# Telex-I.net
KiCad netlist of a schematic drawn in EAGLE
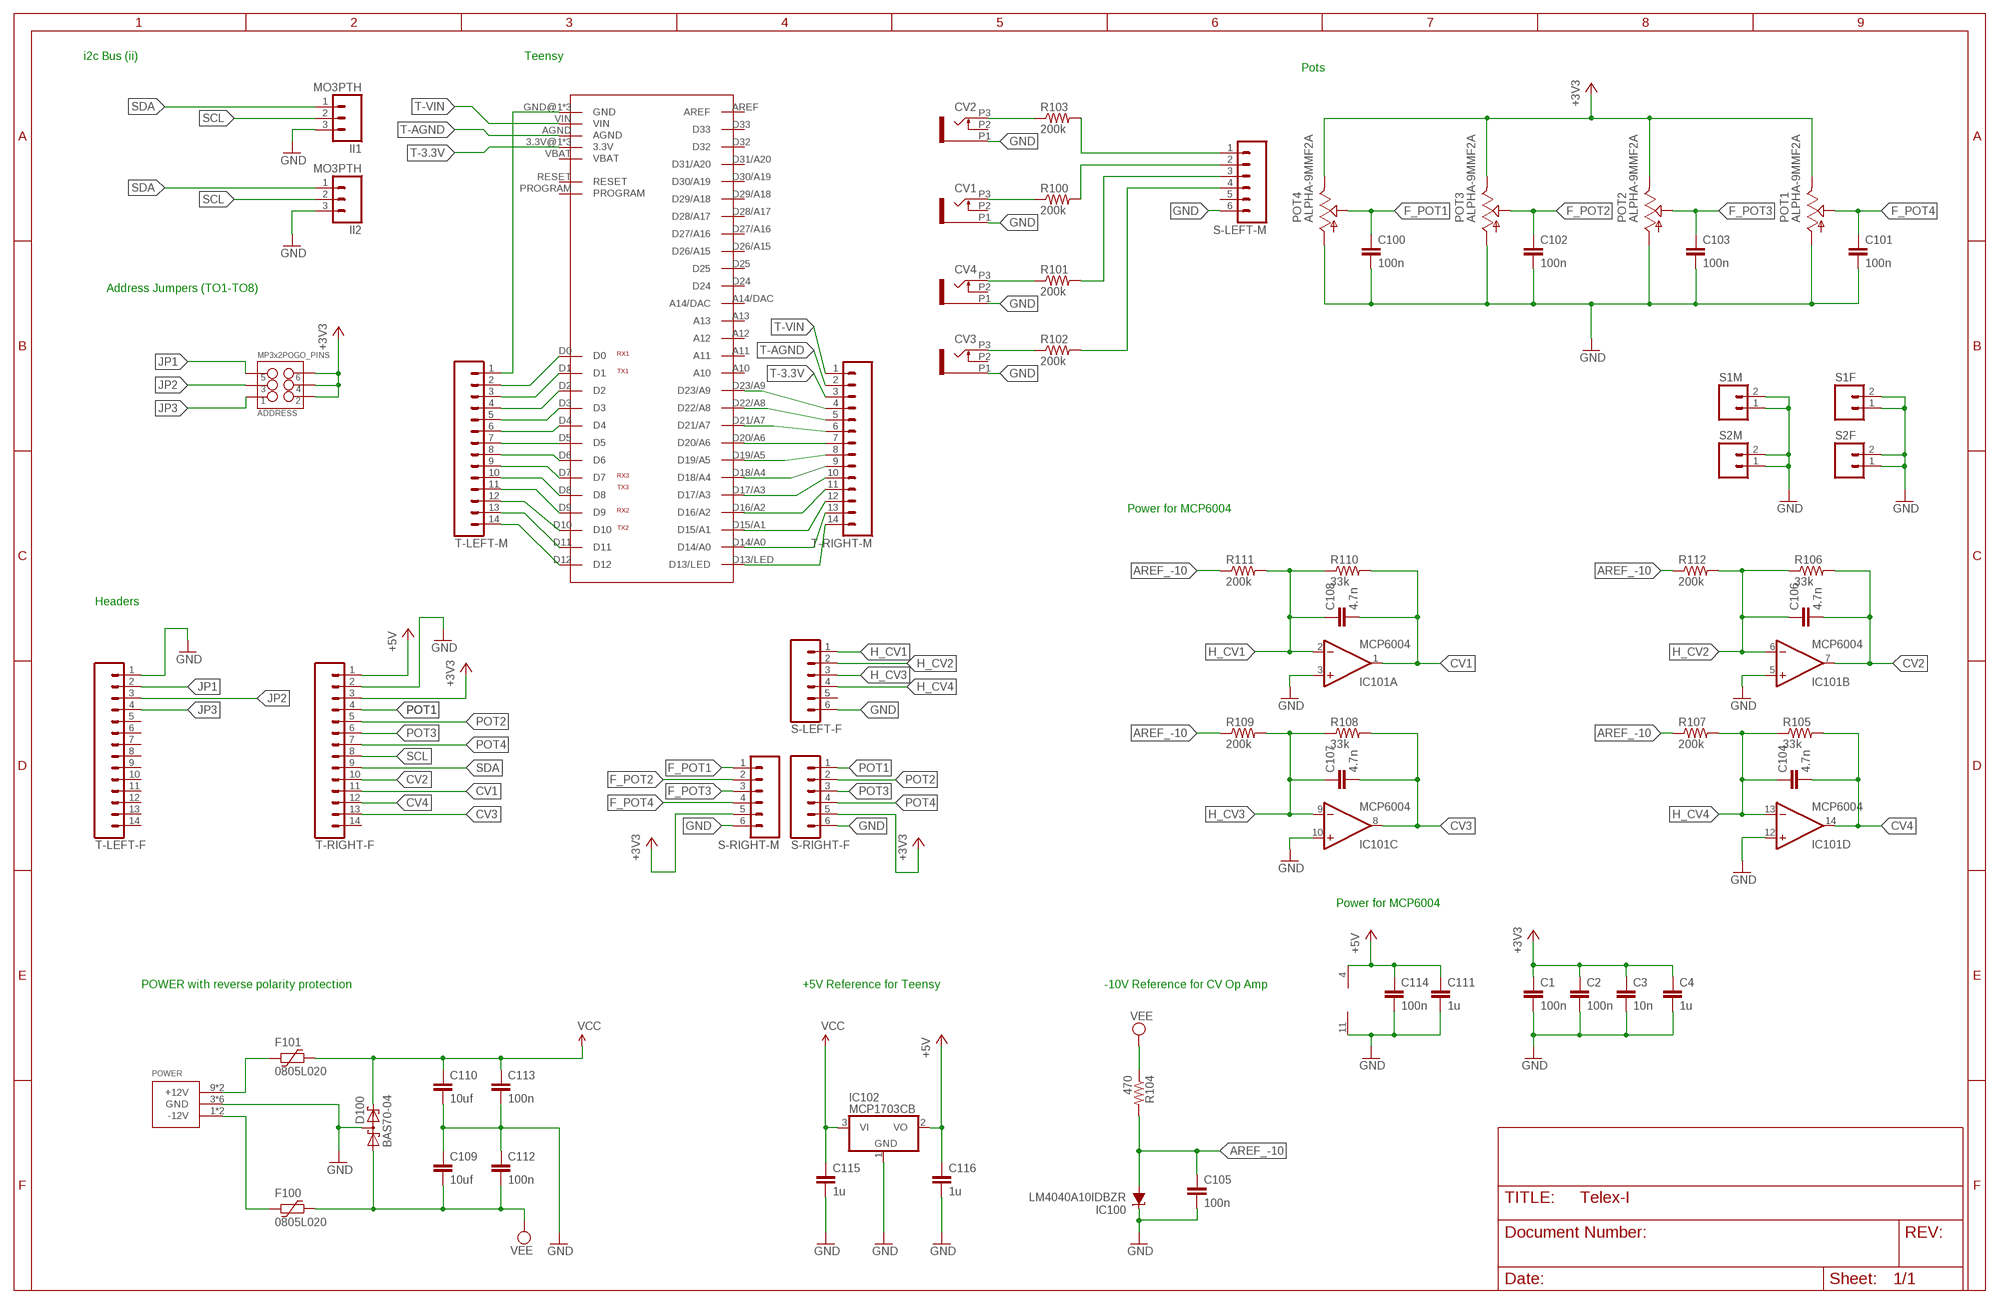
[diagram p0: schematic, sheet 1]

(export (version "E")
  (design (tool "Eeschema 10.0.6"))
  (components
    (comp (ref "ADDRESS")
      (value "MP3x2POGO_PINS")
      (footprint "eagle-import:2X3_POGO")
      (libsource (lib "eagle-import") (part "M03X2POGO_PINS"))
    )
    (comp (ref "C1")
      (value "100n")
      (footprint "eagle-import:0603-CAP")
      (libsource (lib "eagle-import") (part "CAP0603-CAP"))
    )
    (comp (ref "C2")
      (value "100n")
      (footprint "eagle-import:0603-CAP")
      (libsource (lib "eagle-import") (part "CAP0603-CAP"))
    )
    (comp (ref "C3")
      (value "10n")
      (footprint "eagle-import:0603-CAP")
      (libsource (lib "eagle-import") (part "CAP0603-CAP"))
    )
    (comp (ref "C4")
      (value "1u")
      (footprint "eagle-import:0603-CAP")
      (libsource (lib "eagle-import") (part "CAP0603-CAP"))
    )
    (comp (ref "C100")
      (value "100n")
      (footprint "eagle-import:0603-CAP")
      (libsource (lib "eagle-import") (part "CAP0603-CAP"))
    )
    (comp (ref "C101")
      (value "100n")
      (footprint "eagle-import:0603-CAP")
      (libsource (lib "eagle-import") (part "CAP0603-CAP"))
    )
    (comp (ref "C102")
      (value "100n")
      (footprint "eagle-import:0603-CAP")
      (libsource (lib "eagle-import") (part "CAP0603-CAP"))
    )
    (comp (ref "C103")
      (value "100n")
      (footprint "eagle-import:0603-CAP")
      (libsource (lib "eagle-import") (part "CAP0603-CAP"))
    )
    (comp (ref "C104")
      (value "4.7n")
      (footprint "eagle-import:0603-CAP")
      (libsource (lib "eagle-import") (part "CAP0603-CAP"))
    )
    (comp (ref "C105")
      (value "100n")
      (footprint "eagle-import:0603-CAP")
      (libsource (lib "eagle-import") (part "CAP0603-CAP"))
    )
    (comp (ref "C106")
      (value "4.7n")
      (footprint "eagle-import:0603-CAP")
      (libsource (lib "eagle-import") (part "CAP0603-CAP"))
    )
    (comp (ref "C107")
      (value "4.7n")
      (footprint "eagle-import:0603-CAP")
      (libsource (lib "eagle-import") (part "CAP0603-CAP"))
    )
    (comp (ref "C108")
      (value "4.7n")
      (footprint "eagle-import:0603-CAP")
      (libsource (lib "eagle-import") (part "CAP0603-CAP"))
    )
    (comp (ref "C109")
      (value "10uf")
      (footprint "eagle-import:1206")
      (libsource (lib "eagle-import") (part "CAP1206"))
    )
    (comp (ref "C110")
      (value "10uf")
      (footprint "eagle-import:1206")
      (libsource (lib "eagle-import") (part "CAP1206"))
    )
    (comp (ref "C111")
      (value "1u")
      (footprint "eagle-import:0603-CAP")
      (libsource (lib "eagle-import") (part "CAP0603-CAP"))
    )
    (comp (ref "C112")
      (value "100n")
      (footprint "eagle-import:0603-CAP")
      (libsource (lib "eagle-import") (part "CAP0603-CAP"))
    )
    (comp (ref "C113")
      (value "100n")
      (footprint "eagle-import:0603-CAP")
      (libsource (lib "eagle-import") (part "CAP0603-CAP"))
    )
    (comp (ref "C114")
      (value "100n")
      (footprint "eagle-import:0603-CAP")
      (libsource (lib "eagle-import") (part "CAP0603-CAP"))
    )
    (comp (ref "C115")
      (value "1u")
      (footprint "eagle-import:0603-CAP")
      (libsource (lib "eagle-import") (part "CAP0603-CAP"))
    )
    (comp (ref "C116")
      (value "1u")
      (footprint "eagle-import:0603-CAP")
      (libsource (lib "eagle-import") (part "CAP0603-CAP"))
    )
    (comp (ref "CV1")
      (value "EURO_JACKS-7")
      (footprint "eagle-import:WQP_PJ_301M")
      (libsource (lib "eagle-import") (part "EURO_JACKS-7"))
    )
    (comp (ref "CV2")
      (value "EURO_JACKS-7")
      (footprint "eagle-import:WQP_PJ_301M")
      (libsource (lib "eagle-import") (part "EURO_JACKS-7"))
    )
    (comp (ref "CV3")
      (value "EURO_JACKS-7")
      (footprint "eagle-import:WQP_PJ_301M")
      (libsource (lib "eagle-import") (part "EURO_JACKS-7"))
    )
    (comp (ref "CV4")
      (value "EURO_JACKS-7")
      (footprint "eagle-import:WQP_PJ_301M")
      (libsource (lib "eagle-import") (part "EURO_JACKS-7"))
    )
    (comp (ref "D100")
      (value "BAS70-04")
      (footprint "eagle-import:SOT23")
      (libsource (lib "eagle-import") (part "BAS70-04"))
    )
    (comp (ref "F100")
      (value "0805L020")
      (footprint "eagle-import:0805L")
      (fields (field (name "MF") "Littelfuse"))
      (libsource (lib "eagle-import") (part "?0805L020"))
    )
    (comp (ref "F101")
      (value "0805L020")
      (footprint "eagle-import:0805L")
      (fields (field (name "MF") "Littelfuse"))
      (libsource (lib "eagle-import") (part "?0805L020"))
    )
    (comp (ref "IC100")
      (value "LM4040A10IDBZR")
      (footprint "eagle-import:DBZ_R-PDSO-G3")
      (fields (field (name "MPN") "LM4041A12IDBZR"))
      (libsource (lib "eagle-import") (part "LM4041DBZA12"))
    )
    (comp (ref "IC101")
      (value "MCP6004")
      (footprint "eagle-import:SO14")
      (libsource (lib "eagle-import") (part "TL074D"))
    )
    (comp (ref "IC102")
      (value "MCP1703CB")
      (footprint "eagle-import:SOT23")
      (libsource (lib "eagle-import") (part "MCP1703CB"))
    )
    (comp (ref "II1")
      (value "MO3PTH")
      (footprint "eagle-import:1X03")
      (libsource (lib "eagle-import") (part "M03PTH"))
    )
    (comp (ref "II2")
      (value "MO3PTH")
      (footprint "eagle-import:1X03")
      (libsource (lib "eagle-import") (part "M03PTH"))
    )
    (comp (ref "POT1")
      (value "ALPHA-9MMF2A")
      (footprint "eagle-import:EVUF")
      (libsource (lib "eagle-import") (part "ALPHA-9MMAF2"))
    )
    (comp (ref "POT2")
      (value "ALPHA-9MMF2A")
      (footprint "eagle-import:EVUF")
      (libsource (lib "eagle-import") (part "ALPHA-9MMAF2"))
    )
    (comp (ref "POT3")
      (value "ALPHA-9MMF2A")
      (footprint "eagle-import:EVUF")
      (libsource (lib "eagle-import") (part "ALPHA-9MMAF2"))
    )
    (comp (ref "POT4")
      (value "ALPHA-9MMF2A")
      (footprint "eagle-import:EVUF")
      (libsource (lib "eagle-import") (part "ALPHA-9MMAF2"))
    )
    (comp (ref "POWER")
      (value "10-Pin")
      (footprint "eagle-import:POWER_10")
      (libsource (lib "eagle-import") (part "POWER_SIMPLE10"))
    )
    (comp (ref "R100")
      (value "200k")
      (footprint "eagle-import:R0603")
      (libsource (lib "eagle-import") (part "R-US_R0603"))
    )
    (comp (ref "R101")
      (value "200k")
      (footprint "eagle-import:R0603")
      (libsource (lib "eagle-import") (part "R-US_R0603"))
    )
    (comp (ref "R102")
      (value "200k")
      (footprint "eagle-import:R0603")
      (libsource (lib "eagle-import") (part "R-US_R0603"))
    )
    (comp (ref "R103")
      (value "200k")
      (footprint "eagle-import:R0603")
      (libsource (lib "eagle-import") (part "R-US_R0603"))
    )
    (comp (ref "R104")
      (value "470")
      (footprint "eagle-import:R0603")
      (libsource (lib "eagle-import") (part "R-US_R0603"))
    )
    (comp (ref "R105")
      (value "33k")
      (footprint "eagle-import:R0603")
      (libsource (lib "eagle-import") (part "R-US_R0603"))
    )
    (comp (ref "R106")
      (value "33k")
      (footprint "eagle-import:R0603")
      (libsource (lib "eagle-import") (part "R-US_R0603"))
    )
    (comp (ref "R107")
      (value "200k")
      (footprint "eagle-import:R0603")
      (libsource (lib "eagle-import") (part "R-US_R0603"))
    )
    (comp (ref "R108")
      (value "33k")
      (footprint "eagle-import:R0603")
      (libsource (lib "eagle-import") (part "R-US_R0603"))
    )
    (comp (ref "R109")
      (value "200k")
      (footprint "eagle-import:R0603")
      (libsource (lib "eagle-import") (part "R-US_R0603"))
    )
    (comp (ref "R110")
      (value "33k")
      (footprint "eagle-import:R0603")
      (libsource (lib "eagle-import") (part "R-US_R0603"))
    )
    (comp (ref "R111")
      (value "200k")
      (footprint "eagle-import:R0603")
      (libsource (lib "eagle-import") (part "R-US_R0603"))
    )
    (comp (ref "R112")
      (value "200k")
      (footprint "eagle-import:R0603")
      (libsource (lib "eagle-import") (part "R-US_R0603"))
    )
    (comp (ref "S-LEFT-F")
      (value "M06SILK_FEMALE_PTH")
      (footprint "eagle-import:1X06")
      (libsource (lib "eagle-import") (part "M06SILK_FEMALE_PTH"))
    )
    (comp (ref "S-LEFT-M")
      (value "M06SILK_FEMALE_PTH")
      (footprint "eagle-import:1X06")
      (libsource (lib "eagle-import") (part "M06SILK_FEMALE_PTH"))
    )
    (comp (ref "S-RIGHT-F")
      (value "M06SILK_FEMALE_PTH")
      (footprint "eagle-import:1X06")
      (libsource (lib "eagle-import") (part "M06SILK_FEMALE_PTH"))
    )
    (comp (ref "S-RIGHT-M")
      (value "M06SILK_FEMALE_PTH")
      (footprint "eagle-import:1X06")
      (libsource (lib "eagle-import") (part "M06SILK_FEMALE_PTH"))
    )
    (comp (ref "S1F")
      (value "M02PTH")
      (footprint "eagle-import:1X02")
      (libsource (lib "eagle-import") (part "M02PTH"))
    )
    (comp (ref "S1M")
      (value "M02PTH")
      (footprint "eagle-import:1X02")
      (libsource (lib "eagle-import") (part "M02PTH"))
    )
    (comp (ref "S2F")
      (value "M02PTH")
      (footprint "eagle-import:1X02")
      (libsource (lib "eagle-import") (part "M02PTH"))
    )
    (comp (ref "S2M")
      (value "M02PTH")
      (footprint "eagle-import:1X02")
      (libsource (lib "eagle-import") (part "M02PTH"))
    )
    (comp (ref "T-LEFT-F")
      (value "M14")
      (footprint "eagle-import:1X14")
      (libsource (lib "eagle-import") (part "M14"))
    )
    (comp (ref "T-LEFT-M")
      (value "M14")
      (footprint "eagle-import:1X14")
      (libsource (lib "eagle-import") (part "M14"))
    )
    (comp (ref "T-RIGHT-F")
      (value "M14")
      (footprint "eagle-import:1X14")
      (libsource (lib "eagle-import") (part "M14"))
    )
    (comp (ref "T-RIGHT-M")
      (value "M14")
      (footprint "eagle-import:1X14")
      (libsource (lib "eagle-import") (part "M14"))
    )
    (comp (ref "U$1")
      (value "TEENSY3.1_ALL")
      (footprint "eagle-import:TEENSY3.1_ALL")
      (libsource (lib "eagle-import") (part "TEENSY3.1_ALL"))
    )
  )
  (nets
    (net (code "1") (name "+3V3") (class "Default")
      (node (ref "ADDRESS") (pin "P$2") (pinfunction "2_P$2") (pintype "bidirectional"))
      (node (ref "ADDRESS") (pin "P$4") (pinfunction "4_P$4") (pintype "bidirectional"))
      (node (ref "ADDRESS") (pin "P$6") (pinfunction "6_P$6") (pintype "bidirectional"))
      (node (ref "C1") (pin "1") (pinfunction "1_1") (pintype "passive"))
      (node (ref "C2") (pin "1") (pinfunction "1_1") (pintype "passive"))
      (node (ref "C3") (pin "1") (pinfunction "1_1") (pintype "passive"))
      (node (ref "C4") (pin "1") (pinfunction "1_1") (pintype "passive"))
      (node (ref "POT1") (pin "3") (pinfunction "E_3") (pintype "passive"))
      (node (ref "POT2") (pin "3") (pinfunction "E_3") (pintype "passive"))
      (node (ref "POT3") (pin "3") (pinfunction "E_3") (pintype "passive"))
      (node (ref "POT4") (pin "3") (pinfunction "E_3") (pintype "passive"))
      (node (ref "S-RIGHT-F") (pin "5") (pinfunction "5_5") (pintype "passive"))
      (node (ref "S-RIGHT-M") (pin "5") (pinfunction "5_5") (pintype "passive"))
      (node (ref "T-RIGHT-F") (pin "3") (pinfunction "3_3") (pintype "passive"))
    )
    (net (code "2") (name "+5V") (class "Default")
      (node (ref "C111") (pin "1") (pinfunction "1_1") (pintype "passive"))
      (node (ref "C114") (pin "1") (pinfunction "1_1") (pintype "passive"))
      (node (ref "C116") (pin "1") (pinfunction "1_1") (pintype "passive"))
      (node (ref "IC101") (pin "4") (pinfunction "V+_4") (pintype "power_in"))
      (node (ref "IC102") (pin "2") (pinfunction "VO_2") (pintype "passive"))
      (node (ref "T-RIGHT-F") (pin "1") (pinfunction "1_1") (pintype "passive"))
    )
    (net (code "3") (name "AREF_-10") (class "Default")
      (node (ref "C105") (pin "1") (pinfunction "1_1") (pintype "passive"))
      (node (ref "IC100") (pin "2") (pinfunction "A_2") (pintype "passive"))
      (node (ref "R104") (pin "2") (pinfunction "2_2") (pintype "passive"))
      (node (ref "R107") (pin "1") (pinfunction "1_1") (pintype "passive"))
      (node (ref "R109") (pin "1") (pinfunction "1_1") (pintype "passive"))
      (node (ref "R111") (pin "1") (pinfunction "1_1") (pintype "passive"))
      (node (ref "R112") (pin "1") (pinfunction "1_1") (pintype "passive"))
    )
    (net (code "4") (name "CV1") (class "Default")
      (node (ref "C108") (pin "2") (pinfunction "2_2") (pintype "passive"))
      (node (ref "IC101") (pin "1") (pinfunction "OUT_1") (pintype "output"))
      (node (ref "R110") (pin "2") (pinfunction "2_2") (pintype "passive"))
      (node (ref "T-RIGHT-F") (pin "11") (pinfunction "11_11") (pintype "passive"))
    )
    (net (code "5") (name "CV2") (class "Default")
      (node (ref "C106") (pin "2") (pinfunction "2_2") (pintype "passive"))
      (node (ref "IC101") (pin "7") (pinfunction "OUT_7") (pintype "output"))
      (node (ref "R106") (pin "2") (pinfunction "2_2") (pintype "passive"))
      (node (ref "T-RIGHT-F") (pin "10") (pinfunction "10_10") (pintype "passive"))
    )
    (net (code "6") (name "CV3") (class "Default")
      (node (ref "C107") (pin "2") (pinfunction "2_2") (pintype "passive"))
      (node (ref "IC101") (pin "8") (pinfunction "OUT_8") (pintype "output"))
      (node (ref "R108") (pin "2") (pinfunction "2_2") (pintype "passive"))
      (node (ref "T-RIGHT-F") (pin "13") (pinfunction "13_13") (pintype "passive"))
    )
    (net (code "7") (name "CV4") (class "Default")
      (node (ref "C104") (pin "2") (pinfunction "2_2") (pintype "passive"))
      (node (ref "IC101") (pin "14") (pinfunction "OUT_14") (pintype "output"))
      (node (ref "R105") (pin "2") (pinfunction "2_2") (pintype "passive"))
      (node (ref "T-RIGHT-F") (pin "12") (pinfunction "12_12") (pintype "passive"))
    )
    (net (code "8") (name "F_POT1") (class "Default")
      (node (ref "C100") (pin "1") (pinfunction "1_1") (pintype "passive"))
      (node (ref "POT4") (pin "2") (pinfunction "S_2") (pintype "passive"))
      (node (ref "S-RIGHT-M") (pin "1") (pinfunction "1_1") (pintype "passive"))
    )
    (net (code "9") (name "F_POT2") (class "Default")
      (node (ref "C102") (pin "1") (pinfunction "1_1") (pintype "passive"))
      (node (ref "POT3") (pin "2") (pinfunction "S_2") (pintype "passive"))
      (node (ref "S-RIGHT-M") (pin "2") (pinfunction "2_2") (pintype "passive"))
    )
    (net (code "10") (name "F_POT3") (class "Default")
      (node (ref "C103") (pin "1") (pinfunction "1_1") (pintype "passive"))
      (node (ref "POT2") (pin "2") (pinfunction "S_2") (pintype "passive"))
      (node (ref "S-RIGHT-M") (pin "3") (pinfunction "3_3") (pintype "passive"))
    )
    (net (code "11") (name "F_POT4") (class "Default")
      (node (ref "C101") (pin "1") (pinfunction "1_1") (pintype "passive"))
      (node (ref "POT1") (pin "2") (pinfunction "S_2") (pintype "passive"))
      (node (ref "S-RIGHT-M") (pin "4") (pinfunction "4_4") (pintype "passive"))
    )
    (net (code "12") (name "GND") (class "Default")
      (node (ref "C1") (pin "2") (pinfunction "2_2") (pintype "passive"))
      (node (ref "C100") (pin "2") (pinfunction "2_2") (pintype "passive"))
      (node (ref "C101") (pin "2") (pinfunction "2_2") (pintype "passive"))
      (node (ref "C102") (pin "2") (pinfunction "2_2") (pintype "passive"))
      (node (ref "C103") (pin "2") (pinfunction "2_2") (pintype "passive"))
      (node (ref "C105") (pin "2") (pinfunction "2_2") (pintype "passive"))
      (node (ref "C109") (pin "1") (pinfunction "1_1") (pintype "passive"))
      (node (ref "C110") (pin "2") (pinfunction "2_2") (pintype "passive"))
      (node (ref "C111") (pin "2") (pinfunction "2_2") (pintype "passive"))
      (node (ref "C112") (pin "1") (pinfunction "1_1") (pintype "passive"))
      (node (ref "C113") (pin "2") (pinfunction "2_2") (pintype "passive"))
      (node (ref "C114") (pin "2") (pinfunction "2_2") (pintype "passive"))
      (node (ref "C115") (pin "2") (pinfunction "2_2") (pintype "passive"))
      (node (ref "C116") (pin "2") (pinfunction "2_2") (pintype "passive"))
      (node (ref "C2") (pin "2") (pinfunction "2_2") (pintype "passive"))
      (node (ref "C3") (pin "2") (pinfunction "2_2") (pintype "passive"))
      (node (ref "C4") (pin "2") (pinfunction "2_2") (pintype "passive"))
      (node (ref "CV1") (pin "P1") (pinfunction "1_P1") (pintype "passive"))
      (node (ref "CV2") (pin "P1") (pinfunction "1_P1") (pintype "passive"))
      (node (ref "CV3") (pin "P1") (pinfunction "1_P1") (pintype "passive"))
      (node (ref "CV4") (pin "P1") (pinfunction "1_P1") (pintype "passive"))
      (node (ref "D100") (pin "3") (pinfunction "C1A2_3") (pintype "passive"))
      (node (ref "IC100") (pin "1") (pinfunction "C_1") (pintype "passive"))
      (node (ref "IC101") (pin "10") (pinfunction "+IN_10") (pintype "input"))
      (node (ref "IC101") (pin "11") (pinfunction "V-_11") (pintype "power_in"))
      (node (ref "IC101") (pin "12") (pinfunction "+IN_12") (pintype "input"))
      (node (ref "IC101") (pin "3") (pinfunction "+IN_3") (pintype "input"))
      (node (ref "IC101") (pin "5") (pinfunction "+IN_5") (pintype "input"))
      (node (ref "IC102") (pin "1") (pinfunction "GND_1") (pintype "passive"))
      (node (ref "II1") (pin "3") (pinfunction "3_3") (pintype "passive"))
      (node (ref "II2") (pin "3") (pinfunction "3_3") (pintype "passive"))
      (node (ref "POT1") (pin "1") (pinfunction "A_1") (pintype "passive"))
      (node (ref "POT2") (pin "1") (pinfunction "A_1") (pintype "passive"))
      (node (ref "POT3") (pin "1") (pinfunction "A_1") (pintype "passive"))
      (node (ref "POT4") (pin "1") (pinfunction "A_1") (pintype "passive"))
      (node (ref "POWER") (pin "3") (pinfunction "GND_3") (pintype "bidirectional"))
      (node (ref "POWER") (pin "4") (pinfunction "GND_4") (pintype "bidirectional"))
      (node (ref "POWER") (pin "5") (pinfunction "GND_5") (pintype "bidirectional"))
      (node (ref "POWER") (pin "6") (pinfunction "GND_6") (pintype "bidirectional"))
      (node (ref "POWER") (pin "7") (pinfunction "GND_7") (pintype "bidirectional"))
      (node (ref "POWER") (pin "8") (pinfunction "GND_8") (pintype "bidirectional"))
      (node (ref "S-LEFT-F") (pin "6") (pinfunction "6_6") (pintype "passive"))
      (node (ref "S-LEFT-M") (pin "6") (pinfunction "6_6") (pintype "passive"))
      (node (ref "S-RIGHT-F") (pin "6") (pinfunction "6_6") (pintype "passive"))
      (node (ref "S-RIGHT-M") (pin "6") (pinfunction "6_6") (pintype "passive"))
      (node (ref "S1F") (pin "1") (pinfunction "1_1") (pintype "passive"))
      (node (ref "S1F") (pin "2") (pinfunction "2_2") (pintype "passive"))
      (node (ref "S1M") (pin "1") (pinfunction "1_1") (pintype "passive"))
      (node (ref "S1M") (pin "2") (pinfunction "2_2") (pintype "passive"))
      (node (ref "S2F") (pin "1") (pinfunction "1_1") (pintype "passive"))
      (node (ref "S2F") (pin "2") (pinfunction "2_2") (pintype "passive"))
      (node (ref "S2M") (pin "1") (pinfunction "1_1") (pintype "passive"))
      (node (ref "S2M") (pin "2") (pinfunction "2_2") (pintype "passive"))
      (node (ref "T-LEFT-F") (pin "1") (pinfunction "1_1") (pintype "passive"))
      (node (ref "T-RIGHT-F") (pin "2") (pinfunction "2_2") (pintype "passive"))
    )
    (net (code "13") (name "H_CV1") (class "Default")
      (node (ref "C108") (pin "1") (pinfunction "1_1") (pintype "passive"))
      (node (ref "IC101") (pin "2") (pinfunction "-IN_2") (pintype "input"))
      (node (ref "R110") (pin "1") (pinfunction "1_1") (pintype "passive"))
      (node (ref "R111") (pin "2") (pinfunction "2_2") (pintype "passive"))
      (node (ref "S-LEFT-F") (pin "1") (pinfunction "1_1") (pintype "passive"))
    )
    (net (code "14") (name "H_CV2") (class "Default")
      (node (ref "C106") (pin "1") (pinfunction "1_1") (pintype "passive"))
      (node (ref "IC101") (pin "6") (pinfunction "-IN_6") (pintype "input"))
      (node (ref "R106") (pin "1") (pinfunction "1_1") (pintype "passive"))
      (node (ref "R112") (pin "2") (pinfunction "2_2") (pintype "passive"))
      (node (ref "S-LEFT-F") (pin "2") (pinfunction "2_2") (pintype "passive"))
    )
    (net (code "15") (name "H_CV3") (class "Default")
      (node (ref "C107") (pin "1") (pinfunction "1_1") (pintype "passive"))
      (node (ref "IC101") (pin "9") (pinfunction "-IN_9") (pintype "input"))
      (node (ref "R108") (pin "1") (pinfunction "1_1") (pintype "passive"))
      (node (ref "R109") (pin "2") (pinfunction "2_2") (pintype "passive"))
      (node (ref "S-LEFT-F") (pin "3") (pinfunction "3_3") (pintype "passive"))
    )
    (net (code "16") (name "H_CV4") (class "Default")
      (node (ref "C104") (pin "1") (pinfunction "1_1") (pintype "passive"))
      (node (ref "IC101") (pin "13") (pinfunction "-IN_13") (pintype "input"))
      (node (ref "R105") (pin "1") (pinfunction "1_1") (pintype "passive"))
      (node (ref "R107") (pin "2") (pinfunction "2_2") (pintype "passive"))
      (node (ref "S-LEFT-F") (pin "4") (pinfunction "4_4") (pintype "passive"))
    )
    (net (code "17") (name "JP1") (class "Default")
      (node (ref "ADDRESS") (pin "P$5") (pinfunction "5_P$5") (pintype "bidirectional"))
      (node (ref "T-LEFT-F") (pin "2") (pinfunction "2_2") (pintype "passive"))
    )
    (net (code "18") (name "JP2") (class "Default")
      (node (ref "ADDRESS") (pin "P$3") (pinfunction "3_P$3") (pintype "bidirectional"))
      (node (ref "T-LEFT-F") (pin "3") (pinfunction "3_3") (pintype "passive"))
    )
    (net (code "19") (name "JP3") (class "Default")
      (node (ref "ADDRESS") (pin "P$1") (pinfunction "1_P$1") (pintype "bidirectional"))
      (node (ref "T-LEFT-F") (pin "4") (pinfunction "4_4") (pintype "passive"))
    )
    (net (code "20") (name "Net-(CV1-3)") (class "Default")
      (node (ref "CV1") (pin "P3") (pinfunction "3_P3") (pintype "passive"))
      (node (ref "R100") (pin "1") (pinfunction "1_1") (pintype "passive"))
    )
    (net (code "21") (name "Net-(CV2-3)") (class "Default")
      (node (ref "CV2") (pin "P3") (pinfunction "3_P3") (pintype "passive"))
      (node (ref "R103") (pin "1") (pinfunction "1_1") (pintype "passive"))
    )
    (net (code "22") (name "Net-(CV3-3)") (class "Default")
      (node (ref "CV3") (pin "P3") (pinfunction "3_P3") (pintype "passive"))
      (node (ref "R102") (pin "1") (pinfunction "1_1") (pintype "passive"))
    )
    (net (code "23") (name "Net-(CV4-3)") (class "Default")
      (node (ref "CV4") (pin "P3") (pinfunction "3_P3") (pintype "passive"))
      (node (ref "R101") (pin "1") (pinfunction "1_1") (pintype "passive"))
    )
    (net (code "24") (name "Net-(F100-Pad2)") (class "Default")
      (node (ref "F100") (pin "2") (pinfunction "2_2") (pintype "passive"))
      (node (ref "POWER") (pin "1") (pinfunction "-12V_1") (pintype "bidirectional"))
      (node (ref "POWER") (pin "2") (pinfunction "-12V_2") (pintype "bidirectional"))
    )
    (net (code "25") (name "Net-(F101-Pad2)") (class "Default")
      (node (ref "F101") (pin "2") (pinfunction "2_2") (pintype "passive"))
      (node (ref "POWER") (pin "10") (pinfunction "+12V_10") (pintype "bidirectional"))
      (node (ref "POWER") (pin "9") (pinfunction "+12V_9") (pintype "bidirectional"))
    )
    (net (code "26") (name "Net-(R100-Pad2)") (class "Default")
      (node (ref "R100") (pin "2") (pinfunction "2_2") (pintype "passive"))
      (node (ref "S-LEFT-M") (pin "2") (pinfunction "2_2") (pintype "passive"))
    )
    (net (code "27") (name "Net-(R101-Pad2)") (class "Default")
      (node (ref "R101") (pin "2") (pinfunction "2_2") (pintype "passive"))
      (node (ref "S-LEFT-M") (pin "3") (pinfunction "3_3") (pintype "passive"))
    )
    (net (code "28") (name "Net-(R102-Pad2)") (class "Default")
      (node (ref "R102") (pin "2") (pinfunction "2_2") (pintype "passive"))
      (node (ref "S-LEFT-M") (pin "4") (pinfunction "4_4") (pintype "passive"))
    )
    (net (code "29") (name "Net-(R103-Pad2)") (class "Default")
      (node (ref "R103") (pin "2") (pinfunction "2_2") (pintype "passive"))
      (node (ref "S-LEFT-M") (pin "1") (pinfunction "1_1") (pintype "passive"))
    )
    (net (code "30") (name "Net-(T-LEFT-M-Pad1)") (class "Default")
      (node (ref "T-LEFT-M") (pin "1") (pinfunction "1_1") (pintype "passive"))
      (node (ref "U$1") (pin "GND@1") (pinfunction "GND_GND@1") (pintype "bidirectional"))
      (node (ref "U$1") (pin "GND@2") (pinfunction "GND_GND@2") (pintype "bidirectional"))
      (node (ref "U$1") (pin "GND@3") (pinfunction "GND_GND@3") (pintype "bidirectional"))
    )
    (net (code "31") (name "Net-(T-LEFT-M-Pad2)") (class "Default")
      (node (ref "T-LEFT-M") (pin "2") (pinfunction "2_2") (pintype "passive"))
      (node (ref "U$1") (pin "D0") (pinfunction "D0_D0") (pintype "bidirectional"))
    )
    (net (code "32") (name "Net-(T-LEFT-M-Pad3)") (class "Default")
      (node (ref "T-LEFT-M") (pin "3") (pinfunction "3_3") (pintype "passive"))
      (node (ref "U$1") (pin "D1") (pinfunction "D1_D1") (pintype "bidirectional"))
    )
    (net (code "33") (name "Net-(T-LEFT-M-Pad4)") (class "Default")
      (node (ref "T-LEFT-M") (pin "4") (pinfunction "4_4") (pintype "passive"))
      (node (ref "U$1") (pin "D2") (pinfunction "D2_D2") (pintype "bidirectional"))
    )
    (net (code "34") (name "Net-(T-LEFT-M-Pad5)") (class "Default")
      (node (ref "T-LEFT-M") (pin "5") (pinfunction "5_5") (pintype "passive"))
      (node (ref "U$1") (pin "D3") (pinfunction "D3_D3") (pintype "bidirectional"))
    )
    (net (code "35") (name "Net-(T-LEFT-M-Pad6)") (class "Default")
      (node (ref "T-LEFT-M") (pin "6") (pinfunction "6_6") (pintype "passive"))
      (node (ref "U$1") (pin "D4") (pinfunction "D4_D4") (pintype "bidirectional"))
    )
    (net (code "36") (name "Net-(T-LEFT-M-Pad7)") (class "Default")
      (node (ref "T-LEFT-M") (pin "7") (pinfunction "7_7") (pintype "passive"))
      (node (ref "U$1") (pin "D5") (pinfunction "D5_D5") (pintype "bidirectional"))
    )
    (net (code "37") (name "Net-(T-LEFT-M-Pad8)") (class "Default")
      (node (ref "T-LEFT-M") (pin "8") (pinfunction "8_8") (pintype "passive"))
      (node (ref "U$1") (pin "D6") (pinfunction "D6_D6") (pintype "bidirectional"))
    )
    (net (code "38") (name "Net-(T-LEFT-M-Pad9)") (class "Default")
      (node (ref "T-LEFT-M") (pin "9") (pinfunction "9_9") (pintype "passive"))
      (node (ref "U$1") (pin "D7") (pinfunction "D7_D7") (pintype "bidirectional"))
    )
    (net (code "39") (name "Net-(T-LEFT-M-Pad10)") (class "Default")
      (node (ref "T-LEFT-M") (pin "10") (pinfunction "10_10") (pintype "passive"))
      (node (ref "U$1") (pin "D8") (pinfunction "D8_D8") (pintype "bidirectional"))
    )
    (net (code "40") (name "Net-(T-LEFT-M-Pad11)") (class "Default")
      (node (ref "T-LEFT-M") (pin "11") (pinfunction "11_11") (pintype "passive"))
      (node (ref "U$1") (pin "D9") (pinfunction "D9_D9") (pintype "bidirectional"))
    )
    (net (code "41") (name "Net-(T-LEFT-M-Pad12)") (class "Default")
      (node (ref "T-LEFT-M") (pin "12") (pinfunction "12_12") (pintype "passive"))
      (node (ref "U$1") (pin "D10") (pinfunction "D10_D10") (pintype "bidirectional"))
    )
    (net (code "42") (name "Net-(T-LEFT-M-Pad13)") (class "Default")
      (node (ref "T-LEFT-M") (pin "13") (pinfunction "13_13") (pintype "passive"))
      (node (ref "U$1") (pin "D11") (pinfunction "D11_D11") (pintype "bidirectional"))
    )
    (net (code "43") (name "Net-(T-LEFT-M-Pad14)") (class "Default")
      (node (ref "T-LEFT-M") (pin "14") (pinfunction "14_14") (pintype "passive"))
      (node (ref "U$1") (pin "D12") (pinfunction "D12_D12") (pintype "bidirectional"))
    )
    (net (code "44") (name "Net-(T-RIGHT-M-Pad4)") (class "Default")
      (node (ref "T-RIGHT-M") (pin "4") (pinfunction "4_4") (pintype "passive"))
      (node (ref "U$1") (pin "D23/A9") (pinfunction "D23/A9_D23/A9") (pintype "bidirectional"))
    )
    (net (code "45") (name "Net-(T-RIGHT-M-Pad5)") (class "Default")
      (node (ref "T-RIGHT-M") (pin "5") (pinfunction "5_5") (pintype "passive"))
      (node (ref "U$1") (pin "D22/A8") (pinfunction "D22/A8_D22/A8") (pintype "bidirectional"))
    )
    (net (code "46") (name "Net-(T-RIGHT-M-Pad8)") (class "Default")
      (node (ref "T-RIGHT-M") (pin "8") (pinfunction "8_8") (pintype "passive"))
      (node (ref "U$1") (pin "D19/A5") (pinfunction "D19/A5_D19/A5") (pintype "bidirectional"))
    )
    (net (code "47") (name "Net-(T-RIGHT-M-Pad13)") (class "Default")
      (node (ref "T-RIGHT-M") (pin "13") (pinfunction "13_13") (pintype "passive"))
      (node (ref "U$1") (pin "D14/A0") (pinfunction "D14/A0_D14/A0") (pintype "bidirectional"))
    )
    (net (code "48") (name "Net-(T-RIGHT-M-Pad14)") (class "Default")
      (node (ref "T-RIGHT-M") (pin "14") (pinfunction "14_14") (pintype "passive"))
      (node (ref "U$1") (pin "D13/LED") (pinfunction "D13/LED_D13/LED") (pintype "bidirectional"))
    )
    (net (code "49") (name "POT1") (class "Default")
      (node (ref "S-RIGHT-F") (pin "1") (pinfunction "1_1") (pintype "passive"))
      (node (ref "T-RIGHT-F") (pin "4") (pinfunction "4_4") (pintype "passive"))
    )
    (net (code "50") (name "POT2") (class "Default")
      (node (ref "S-RIGHT-F") (pin "2") (pinfunction "2_2") (pintype "passive"))
      (node (ref "T-RIGHT-F") (pin "5") (pinfunction "5_5") (pintype "passive"))
    )
    (net (code "51") (name "POT3") (class "Default")
      (node (ref "S-RIGHT-F") (pin "3") (pinfunction "3_3") (pintype "passive"))
      (node (ref "T-RIGHT-F") (pin "6") (pinfunction "6_6") (pintype "passive"))
    )
    (net (code "52") (name "POT4") (class "Default")
      (node (ref "S-RIGHT-F") (pin "4") (pinfunction "4_4") (pintype "passive"))
      (node (ref "T-RIGHT-F") (pin "7") (pinfunction "7_7") (pintype "passive"))
    )
    (net (code "53") (name "SCL") (class "Default")
      (node (ref "II1") (pin "2") (pinfunction "2_2") (pintype "passive"))
      (node (ref "II2") (pin "2") (pinfunction "2_2") (pintype "passive"))
      (node (ref "T-RIGHT-F") (pin "8") (pinfunction "8_8") (pintype "passive"))
    )
    (net (code "54") (name "SDA") (class "Default")
      (node (ref "II1") (pin "1") (pinfunction "1_1") (pintype "passive"))
      (node (ref "II2") (pin "1") (pinfunction "1_1") (pintype "passive"))
      (node (ref "T-RIGHT-F") (pin "9") (pinfunction "9_9") (pintype "passive"))
    )
    (net (code "55") (name "T-3.3V") (class "Default")
      (node (ref "T-RIGHT-M") (pin "3") (pinfunction "3_3") (pintype "passive"))
      (node (ref "U$1") (pin "3.3V@1") (pinfunction "3.3V_3.3V@1") (pintype "bidirectional"))
      (node (ref "U$1") (pin "3.3V@2") (pinfunction "3.3V_3.3V@2") (pintype "bidirectional"))
      (node (ref "U$1") (pin "3.3V@3") (pinfunction "3.3V_3.3V@3") (pintype "bidirectional"))
    )
    (net (code "56") (name "T-AGND") (class "Default")
      (node (ref "T-RIGHT-M") (pin "2") (pinfunction "2_2") (pintype "passive"))
      (node (ref "U$1") (pin "AGND") (pinfunction "AGND_AGND") (pintype "bidirectional"))
    )
    (net (code "57") (name "T-VIN") (class "Default")
      (node (ref "T-RIGHT-M") (pin "1") (pinfunction "1_1") (pintype "passive"))
      (node (ref "U$1") (pin "VIN") (pinfunction "VIN_VIN") (pintype "bidirectional"))
    )
    (net (code "58") (name "VCC") (class "Default")
      (node (ref "C110") (pin "1") (pinfunction "1_1") (pintype "passive"))
      (node (ref "C113") (pin "1") (pinfunction "1_1") (pintype "passive"))
      (node (ref "C115") (pin "1") (pinfunction "1_1") (pintype "passive"))
      (node (ref "D100") (pin "2") (pinfunction "C2_2") (pintype "passive"))
      (node (ref "F101") (pin "1") (pinfunction "1_1") (pintype "passive"))
      (node (ref "IC102") (pin "3") (pinfunction "VI_3") (pintype "input"))
    )
    (net (code "59") (name "VEE") (class "Default")
      (node (ref "C109") (pin "2") (pinfunction "2_2") (pintype "passive"))
      (node (ref "C112") (pin "2") (pinfunction "2_2") (pintype "passive"))
      (node (ref "D100") (pin "1") (pinfunction "A1_1") (pintype "passive"))
      (node (ref "F100") (pin "1") (pinfunction "1_1") (pintype "passive"))
      (node (ref "R104") (pin "1") (pinfunction "1_1") (pintype "passive"))
    )
    (net (code "60") (name "unconnected-(CV1-2-PadP2)") (class "Default")
      (node (ref "CV1") (pin "P2") (pinfunction "2_P2") (pintype "passive"))
    )
    (net (code "61") (name "unconnected-(CV2-2-PadP2)") (class "Default")
      (node (ref "CV2") (pin "P2") (pinfunction "2_P2") (pintype "passive"))
    )
    (net (code "62") (name "unconnected-(CV3-2-PadP2)") (class "Default")
      (node (ref "CV3") (pin "P2") (pinfunction "2_P2") (pintype "passive"))
    )
    (net (code "63") (name "unconnected-(CV4-2-PadP2)") (class "Default")
      (node (ref "CV4") (pin "P2") (pinfunction "2_P2") (pintype "passive"))
    )
    (net (code "64") (name "unconnected-(S-LEFT-F-Pad5)") (class "Default")
      (node (ref "S-LEFT-F") (pin "5") (pinfunction "5_5") (pintype "passive"))
    )
    (net (code "65") (name "unconnected-(S-LEFT-M-Pad5)") (class "Default")
      (node (ref "S-LEFT-M") (pin "5") (pinfunction "5_5") (pintype "passive"))
    )
    (net (code "66") (name "unconnected-(T-LEFT-F-Pad5)") (class "Default")
      (node (ref "T-LEFT-F") (pin "5") (pinfunction "5_5") (pintype "passive"))
    )
    (net (code "67") (name "unconnected-(T-LEFT-F-Pad6)") (class "Default")
      (node (ref "T-LEFT-F") (pin "6") (pinfunction "6_6") (pintype "passive"))
    )
    (net (code "68") (name "unconnected-(T-LEFT-F-Pad7)") (class "Default")
      (node (ref "T-LEFT-F") (pin "7") (pinfunction "7_7") (pintype "passive"))
    )
    (net (code "69") (name "unconnected-(T-LEFT-F-Pad8)") (class "Default")
      (node (ref "T-LEFT-F") (pin "8") (pinfunction "8_8") (pintype "passive"))
    )
    (net (code "70") (name "unconnected-(T-LEFT-F-Pad9)") (class "Default")
      (node (ref "T-LEFT-F") (pin "9") (pinfunction "9_9") (pintype "passive"))
    )
    (net (code "71") (name "unconnected-(T-LEFT-F-Pad10)") (class "Default")
      (node (ref "T-LEFT-F") (pin "10") (pinfunction "10_10") (pintype "passive"))
    )
    (net (code "72") (name "unconnected-(T-LEFT-F-Pad11)") (class "Default")
      (node (ref "T-LEFT-F") (pin "11") (pinfunction "11_11") (pintype "passive"))
    )
    (net (code "73") (name "unconnected-(T-LEFT-F-Pad12)") (class "Default")
      (node (ref "T-LEFT-F") (pin "12") (pinfunction "12_12") (pintype "passive"))
    )
    (net (code "74") (name "unconnected-(T-LEFT-F-Pad13)") (class "Default")
      (node (ref "T-LEFT-F") (pin "13") (pinfunction "13_13") (pintype "passive"))
    )
    (net (code "75") (name "unconnected-(T-LEFT-F-Pad14)") (class "Default")
      (node (ref "T-LEFT-F") (pin "14") (pinfunction "14_14") (pintype "passive"))
    )
    (net (code "76") (name "unconnected-(T-RIGHT-F-Pad14)") (class "Default")
      (node (ref "T-RIGHT-F") (pin "14") (pinfunction "14_14") (pintype "passive"))
    )
    (net (code "77") (name "unconnected-(T-RIGHT-M-Pad6)") (class "Default")
      (node (ref "T-RIGHT-M") (pin "6") (pinfunction "6_6") (pintype "passive"))
    )
    (net (code "78") (name "unconnected-(T-RIGHT-M-Pad7)") (class "Default")
      (node (ref "T-RIGHT-M") (pin "7") (pinfunction "7_7") (pintype "passive"))
    )
    (net (code "79") (name "unconnected-(T-RIGHT-M-Pad9)") (class "Default")
      (node (ref "T-RIGHT-M") (pin "9") (pinfunction "9_9") (pintype "passive"))
    )
    (net (code "80") (name "unconnected-(T-RIGHT-M-Pad10)") (class "Default")
      (node (ref "T-RIGHT-M") (pin "10") (pinfunction "10_10") (pintype "passive"))
    )
    (net (code "81") (name "unconnected-(T-RIGHT-M-Pad11)") (class "Default")
      (node (ref "T-RIGHT-M") (pin "11") (pinfunction "11_11") (pintype "passive"))
    )
    (net (code "82") (name "unconnected-(T-RIGHT-M-Pad12)") (class "Default")
      (node (ref "T-RIGHT-M") (pin "12") (pinfunction "12_12") (pintype "passive"))
    )
    (net (code "83") (name "unconnected-(U$1-PadA10)") (class "Default")
      (node (ref "U$1") (pin "A10") (pinfunction "A10_A10") (pintype "bidirectional"))
    )
    (net (code "84") (name "unconnected-(U$1-PadA11)") (class "Default")
      (node (ref "U$1") (pin "A11") (pinfunction "A11_A11") (pintype "bidirectional"))
    )
    (net (code "85") (name "unconnected-(U$1-PadA12)") (class "Default")
      (node (ref "U$1") (pin "A12") (pinfunction "A12_A12") (pintype "bidirectional"))
    )
    (net (code "86") (name "unconnected-(U$1-PadA13)") (class "Default")
      (node (ref "U$1") (pin "A13") (pinfunction "A13_A13") (pintype "bidirectional"))
    )
    (net (code "87") (name "unconnected-(U$1-PadA14{slash}DAC)") (class "Default")
      (node (ref "U$1") (pin "A14/DAC") (pinfunction "A14/DAC_A14/DAC") (pintype "bidirectional"))
    )
    (net (code "88") (name "unconnected-(U$1-PadAREF)") (class "Default")
      (node (ref "U$1") (pin "AREF") (pinfunction "AREF_AREF") (pintype "bidirectional"))
    )
    (net (code "89") (name "unconnected-(U$1-PadD15{slash}A1)") (class "Default")
      (node (ref "U$1") (pin "D15/A1") (pinfunction "D15/A1_D15/A1") (pintype "bidirectional"))
    )
    (net (code "90") (name "unconnected-(U$1-PadD16{slash}A2)") (class "Default")
      (node (ref "U$1") (pin "D16/A2") (pinfunction "D16/A2_D16/A2") (pintype "bidirectional"))
    )
    (net (code "91") (name "unconnected-(U$1-PadD17{slash}A3)") (class "Default")
      (node (ref "U$1") (pin "D17/A3") (pinfunction "D17/A3_D17/A3") (pintype "bidirectional"))
    )
    (net (code "92") (name "unconnected-(U$1-PadD18{slash}A4)") (class "Default")
      (node (ref "U$1") (pin "D18/A4") (pinfunction "D18/A4_D18/A4") (pintype "bidirectional"))
    )
    (net (code "93") (name "unconnected-(U$1-PadD20{slash}A6)") (class "Default")
      (node (ref "U$1") (pin "D20/A6") (pinfunction "D20/A6_D20/A6") (pintype "bidirectional"))
    )
    (net (code "94") (name "unconnected-(U$1-PadD21{slash}A7)") (class "Default")
      (node (ref "U$1") (pin "D21/A7") (pinfunction "D21/A7_D21/A7") (pintype "bidirectional"))
    )
    (net (code "95") (name "unconnected-(U$1-PadD24)") (class "Default")
      (node (ref "U$1") (pin "D24") (pinfunction "D24_D24") (pintype "bidirectional"))
    )
    (net (code "96") (name "unconnected-(U$1-PadD25)") (class "Default")
      (node (ref "U$1") (pin "D25") (pinfunction "D25_D25") (pintype "bidirectional"))
    )
    (net (code "97") (name "unconnected-(U$1-PadD26{slash}A15)") (class "Default")
      (node (ref "U$1") (pin "D26/A15") (pinfunction "D26/A15_D26/A15") (pintype "bidirectional"))
    )
    (net (code "98") (name "unconnected-(U$1-PadD27{slash}A16)") (class "Default")
      (node (ref "U$1") (pin "D27/A16") (pinfunction "D27/A16_D27/A16") (pintype "bidirectional"))
    )
    (net (code "99") (name "unconnected-(U$1-PadD28{slash}A17)") (class "Default")
      (node (ref "U$1") (pin "D28/A17") (pinfunction "D28/A17_D28/A17") (pintype "bidirectional"))
    )
    (net (code "100") (name "unconnected-(U$1-PadD29{slash}A18)") (class "Default")
      (node (ref "U$1") (pin "D29/A18") (pinfunction "D29/A18_D29/A18") (pintype "bidirectional"))
    )
    (net (code "101") (name "unconnected-(U$1-PadD30{slash}A19)") (class "Default")
      (node (ref "U$1") (pin "D30/A19") (pinfunction "D30/A19_D30/A19") (pintype "bidirectional"))
    )
    (net (code "102") (name "unconnected-(U$1-PadD31{slash}A20)") (class "Default")
      (node (ref "U$1") (pin "D31/A20") (pinfunction "D31/A20_D31/A20") (pintype "bidirectional"))
    )
    (net (code "103") (name "unconnected-(U$1-PadD32)") (class "Default")
      (node (ref "U$1") (pin "D32") (pinfunction "D32_D32") (pintype "bidirectional"))
    )
    (net (code "104") (name "unconnected-(U$1-PadD33)") (class "Default")
      (node (ref "U$1") (pin "D33") (pinfunction "D33_D33") (pintype "bidirectional"))
    )
    (net (code "105") (name "unconnected-(U$1-PadPROGRAM)") (class "Default")
      (node (ref "U$1") (pin "PROGRAM") (pinfunction "PROGRAM_PROGRAM") (pintype "bidirectional"))
    )
    (net (code "106") (name "unconnected-(U$1-PadRESET)") (class "Default")
      (node (ref "U$1") (pin "RESET") (pinfunction "RESET_RESET") (pintype "bidirectional"))
    )
    (net (code "107") (name "unconnected-(U$1-PadVBAT)") (class "Default")
      (node (ref "U$1") (pin "VBAT") (pinfunction "VBAT_VBAT") (pintype "bidirectional"))
    )
  )
)
